# epd_board.net
KiCad netlist of a schematic drawn in EAGLE
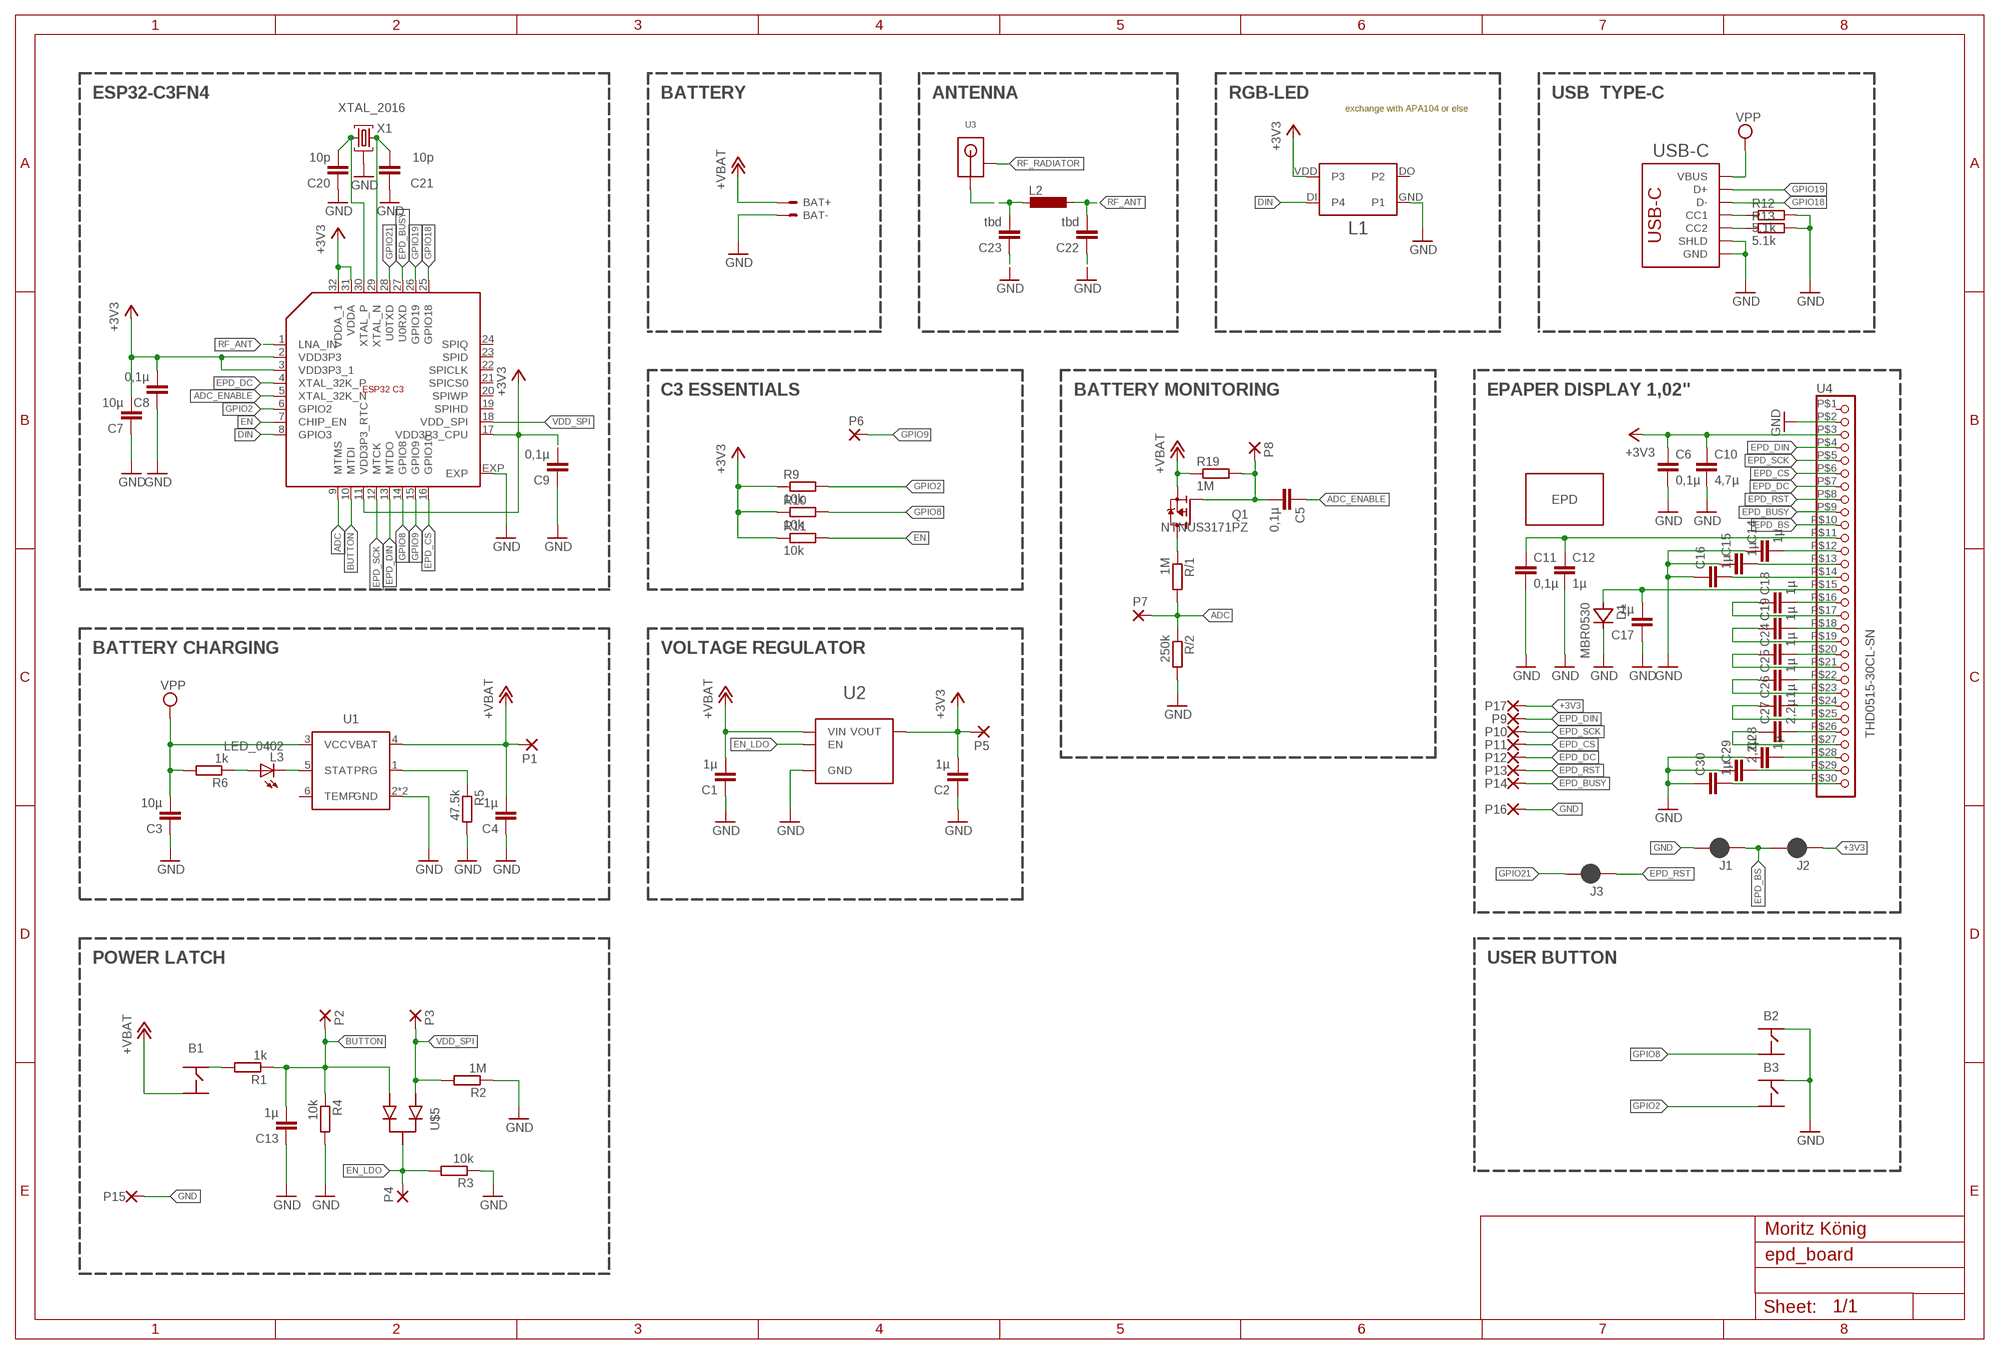
[diagram p0: schematic, sheet 1]

(export (version "E")
  (design (tool "Eeschema 10.0.6"))
  (components
    (comp (ref "B1")
      (value "BUTTON_4PIN_TS-1070A")
      (footprint "eagle-import:BUTTON_WHITE_SMD")
      (libsource (lib "eagle-import") (part "BUTTON_4PIN_TS-1070A"))
    )
    (comp (ref "B2")
      (value "PTS840ESDGMSMTRLFS")
      (footprint "eagle-import:PTS840ESDGMSMTRLFS")
      (libsource (lib "eagle-import") (part "PTS840ESDGMSMTRLFS"))
    )
    (comp (ref "B3")
      (value "PTS840ESDGMSMTRLFS")
      (footprint "eagle-import:PTS840ESDGMSMTRLFS")
      (libsource (lib "eagle-import") (part "PTS840ESDGMSMTRLFS"))
    )
    (comp (ref "BAT+")
      (value "TP/SP-1.5X1.0")
      (footprint "eagle-import:SOLDERPAD_1.5X1.0")
      (libsource (lib "eagle-import") (part "TP/SP-1.5X1.0"))
    )
    (comp (ref "BAT-")
      (value "TP/SP-1.5X1.0")
      (footprint "eagle-import:SOLDERPAD_1.5X1.0")
      (libsource (lib "eagle-import") (part "TP/SP-1.5X1.0"))
    )
    (comp (ref "C1")
      (value "1µ")
      (footprint "eagle-import:C0402_S")
      (libsource (lib "eagle-import") (part "C0402_S"))
    )
    (comp (ref "C2")
      (value "1µ")
      (footprint "eagle-import:C0402_S")
      (libsource (lib "eagle-import") (part "C0402_S"))
    )
    (comp (ref "C3")
      (value "10µ")
      (footprint "eagle-import:C0402_S")
      (libsource (lib "eagle-import") (part "C0402_S"))
    )
    (comp (ref "C4")
      (value "1µ")
      (footprint "eagle-import:C0402_S")
      (libsource (lib "eagle-import") (part "C0402_S"))
    )
    (comp (ref "C5")
      (value "0,1µ")
      (footprint "eagle-import:C0402_S")
      (libsource (lib "eagle-import") (part "C0402_S"))
    )
    (comp (ref "C6")
      (value "0,1µ")
      (footprint "eagle-import:C0402_S")
      (libsource (lib "eagle-import") (part "C0402_S"))
    )
    (comp (ref "C7")
      (value "10µ")
      (footprint "eagle-import:C0402_S")
      (libsource (lib "eagle-import") (part "C0402_S"))
    )
    (comp (ref "C8")
      (value "0,1µ")
      (footprint "eagle-import:C0402_S")
      (libsource (lib "eagle-import") (part "C0402_S"))
    )
    (comp (ref "C9")
      (value "0,1µ")
      (footprint "eagle-import:C0402_S")
      (libsource (lib "eagle-import") (part "C0402_S"))
    )
    (comp (ref "C10")
      (value "4,7µ")
      (footprint "eagle-import:C0402_S")
      (libsource (lib "eagle-import") (part "C0402_S"))
    )
    (comp (ref "C11")
      (value "0,1µ")
      (footprint "eagle-import:C0402_S")
      (libsource (lib "eagle-import") (part "C0402_S"))
    )
    (comp (ref "C12")
      (value "1µ")
      (footprint "eagle-import:C0402_S")
      (libsource (lib "eagle-import") (part "C0402_S"))
    )
    (comp (ref "C13")
      (value "1µ")
      (footprint "eagle-import:C0402_S")
      (libsource (lib "eagle-import") (part "C0402_S"))
    )
    (comp (ref "C14")
      (value "1µ")
      (footprint "eagle-import:C0402_S")
      (libsource (lib "eagle-import") (part "C0402_S"))
    )
    (comp (ref "C15")
      (value "1µ")
      (footprint "eagle-import:C0402_S")
      (libsource (lib "eagle-import") (part "C0402_S"))
    )
    (comp (ref "C16")
      (value "1µ")
      (footprint "eagle-import:C0402_S")
      (libsource (lib "eagle-import") (part "C0402_S"))
    )
    (comp (ref "C17")
      (value "1µ")
      (footprint "eagle-import:C0402_S")
      (libsource (lib "eagle-import") (part "C0402_S"))
    )
    (comp (ref "C18")
      (value "1µ")
      (footprint "eagle-import:C0402_S")
      (libsource (lib "eagle-import") (part "C0402_S"))
    )
    (comp (ref "C19")
      (value "1µ")
      (footprint "eagle-import:C0402_S")
      (libsource (lib "eagle-import") (part "C0402_S"))
    )
    (comp (ref "C20")
      (value "10p")
      (footprint "eagle-import:C0402_S")
      (libsource (lib "eagle-import") (part "C0402_S"))
    )
    (comp (ref "C21")
      (value "10p")
      (footprint "eagle-import:C0402_S")
      (libsource (lib "eagle-import") (part "C0402_S"))
    )
    (comp (ref "C22")
      (value "tbd")
      (footprint "eagle-import:C0201")
      (libsource (lib "eagle-import") (part "C0201"))
    )
    (comp (ref "C23")
      (value "tbd")
      (footprint "eagle-import:C0201")
      (libsource (lib "eagle-import") (part "C0201"))
    )
    (comp (ref "C24")
      (value "1µ")
      (footprint "eagle-import:C0402_S")
      (libsource (lib "eagle-import") (part "C0402_S"))
    )
    (comp (ref "C25")
      (value "1µ")
      (footprint "eagle-import:C0402_S")
      (libsource (lib "eagle-import") (part "C0402_S"))
    )
    (comp (ref "C26")
      (value "1µ")
      (footprint "eagle-import:C0402_S")
      (libsource (lib "eagle-import") (part "C0402_S"))
    )
    (comp (ref "C27")
      (value "2,2µ")
      (footprint "eagle-import:C0402_S")
      (libsource (lib "eagle-import") (part "C0402_S"))
    )
    (comp (ref "C28")
      (value "1µ")
      (footprint "eagle-import:C0402_S")
      (libsource (lib "eagle-import") (part "C0402_S"))
    )
    (comp (ref "C29")
      (value "2,2µ")
      (footprint "eagle-import:C0402_S")
      (libsource (lib "eagle-import") (part "C0402_S"))
    )
    (comp (ref "C30")
      (value "1µ")
      (footprint "eagle-import:C0402_S")
      (libsource (lib "eagle-import") (part "C0402_S"))
    )
    (comp (ref "D1")
      (value "MBR0530")
      (footprint "eagle-import:SOD123")
      (libsource (lib "eagle-import") (part "MBR0520"))
    )
    (comp (ref "ESP1")
      (value "ESP32_C3_QFN32")
      (footprint "eagle-import:QFN32")
      (libsource (lib "eagle-import") (part "ESP32_C3_QFN32"))
    )
    (comp (ref "J1")
      (value "SMT_JUMPER_2_NC_PASTE")
      (footprint "eagle-import:JUMPER_SMALL")
      (libsource (lib "eagle-import") (part "SMT_JUMPER_2_NC_PASTE"))
    )
    (comp (ref "J2")
      (value "SMT_JUMPER_2_NC_PASTE")
      (footprint "eagle-import:JUMPER_SMALL")
      (libsource (lib "eagle-import") (part "SMT_JUMPER_2_NC_PASTE"))
    )
    (comp (ref "J3")
      (value "SMT_JUMPER_2_NC_PASTE")
      (footprint "eagle-import:JUMPER_SMALL")
      (libsource (lib "eagle-import") (part "SMT_JUMPER_2_NC_PASTE"))
    )
    (comp (ref "L1")
      (value "WS2812_2020")
      (footprint "eagle-import:WS2812_2020")
      (libsource (lib "eagle-import") (part "WS2812_2020"))
    )
    (comp (ref "L2")
      (value "L0201")
      (footprint "eagle-import:L0201")
      (libsource (lib "eagle-import") (part "L0201"))
    )
    (comp (ref "L3")
      (value "LED_0402")
      (footprint "eagle-import:CHIPLED_0402")
      (libsource (lib "eagle-import") (part "LED_0402"))
    )
    (comp (ref "P1")
      (value "SMD-R1")
      (footprint "eagle-import:SMD-R1")
      (libsource (lib "eagle-import") (part "SMD-R1"))
    )
    (comp (ref "P2")
      (value "SMD-R1")
      (footprint "eagle-import:SMD-R1")
      (libsource (lib "eagle-import") (part "SMD-R1"))
    )
    (comp (ref "P3")
      (value "SMD-R1")
      (footprint "eagle-import:SMD-R1")
      (libsource (lib "eagle-import") (part "SMD-R1"))
    )
    (comp (ref "P4")
      (value "SMD-R1")
      (footprint "eagle-import:SMD-R1")
      (libsource (lib "eagle-import") (part "SMD-R1"))
    )
    (comp (ref "P5")
      (value "SMD-R1")
      (footprint "eagle-import:SMD-R1")
      (libsource (lib "eagle-import") (part "SMD-R1"))
    )
    (comp (ref "P6")
      (value "SMD-R1")
      (footprint "eagle-import:SMD-R1")
      (libsource (lib "eagle-import") (part "SMD-R1"))
    )
    (comp (ref "P7")
      (value "SMD-R1")
      (footprint "eagle-import:SMD-R1")
      (libsource (lib "eagle-import") (part "SMD-R1"))
    )
    (comp (ref "P8")
      (value "SMD-R1")
      (footprint "eagle-import:SMD-R1")
      (libsource (lib "eagle-import") (part "SMD-R1"))
    )
    (comp (ref "P9")
      (value "SMD-R1")
      (footprint "eagle-import:SMD-R1")
      (libsource (lib "eagle-import") (part "SMD-R1"))
    )
    (comp (ref "P10")
      (value "SMD-R1")
      (footprint "eagle-import:SMD-R1")
      (libsource (lib "eagle-import") (part "SMD-R1"))
    )
    (comp (ref "P11")
      (value "SMD-R1")
      (footprint "eagle-import:SMD-R1")
      (libsource (lib "eagle-import") (part "SMD-R1"))
    )
    (comp (ref "P12")
      (value "SMD-R1")
      (footprint "eagle-import:SMD-R1")
      (libsource (lib "eagle-import") (part "SMD-R1"))
    )
    (comp (ref "P13")
      (value "SMD-R1")
      (footprint "eagle-import:SMD-R1")
      (libsource (lib "eagle-import") (part "SMD-R1"))
    )
    (comp (ref "P14")
      (value "SMD-R1")
      (footprint "eagle-import:SMD-R1")
      (libsource (lib "eagle-import") (part "SMD-R1"))
    )
    (comp (ref "P15")
      (value "SMD-R1")
      (footprint "eagle-import:SMD-R1")
      (libsource (lib "eagle-import") (part "SMD-R1"))
    )
    (comp (ref "P16")
      (value "SMD-R1")
      (footprint "eagle-import:SMD-R1")
      (libsource (lib "eagle-import") (part "SMD-R1"))
    )
    (comp (ref "P17")
      (value "SMD-R1")
      (footprint "eagle-import:SMD-R1")
      (libsource (lib "eagle-import") (part "SMD-R1"))
    )
    (comp (ref "Q1")
      (value "NTNUS3171PZ")
      (footprint "eagle-import:SOT1123")
      (libsource (lib "eagle-import") (part "NTNUS3171PZ"))
    )
    (comp (ref "R/1")
      (value "1M")
      (footprint "eagle-import:R0402")
      (libsource (lib "eagle-import") (part "R0402"))
    )
    (comp (ref "R/2")
      (value "250k")
      (footprint "eagle-import:R0402")
      (libsource (lib "eagle-import") (part "R0402"))
    )
    (comp (ref "R1")
      (value "1k")
      (footprint "eagle-import:R0402")
      (libsource (lib "eagle-import") (part "R0402"))
    )
    (comp (ref "R2")
      (value "1M")
      (footprint "eagle-import:R0402")
      (libsource (lib "eagle-import") (part "R0402"))
    )
    (comp (ref "R3")
      (value "10k")
      (footprint "eagle-import:R0402")
      (libsource (lib "eagle-import") (part "R0402"))
    )
    (comp (ref "R4")
      (value "10k")
      (footprint "eagle-import:R0402")
      (libsource (lib "eagle-import") (part "R0402"))
    )
    (comp (ref "R5")
      (value "47.5k")
      (footprint "eagle-import:R0402")
      (libsource (lib "eagle-import") (part "R0402"))
    )
    (comp (ref "R6")
      (value "1k")
      (footprint "eagle-import:R0402")
      (libsource (lib "eagle-import") (part "R0402"))
    )
    (comp (ref "R9")
      (value "10k")
      (footprint "eagle-import:R0402")
      (libsource (lib "eagle-import") (part "R0402"))
    )
    (comp (ref "R10")
      (value "10k")
      (footprint "eagle-import:R0402")
      (libsource (lib "eagle-import") (part "R0402"))
    )
    (comp (ref "R11")
      (value "10k")
      (footprint "eagle-import:R0402")
      (libsource (lib "eagle-import") (part "R0402"))
    )
    (comp (ref "R12")
      (value "5.1k")
      (footprint "eagle-import:R0402")
      (libsource (lib "eagle-import") (part "R0402"))
    )
    (comp (ref "R13")
      (value "5.1k")
      (footprint "eagle-import:R0402")
      (libsource (lib "eagle-import") (part "R0402"))
    )
    (comp (ref "R19")
      (value "1M")
      (footprint "eagle-import:R0402")
      (libsource (lib "eagle-import") (part "R0402"))
    )
    (comp (ref "U$2")
      (value "EPD-102-30PIN-TW")
      (footprint "eagle-import:EPD-102-30PIN-TW")
      (libsource (lib "eagle-import") (part "EPD-102-30PIN-TW"))
    )
    (comp (ref "U$5")
      (value "DAN222")
      (footprint "eagle-import:SOT523")
      (libsource (lib "eagle-import") (part "DAN222"))
    )
    (comp (ref "U1")
      (value "WS4518D")
      (footprint "eagle-import:DFN-6")
      (libsource (lib "eagle-import") (part "WS4518D"))
    )
    (comp (ref "U2")
      (value "MIC5504")
      (footprint "eagle-import:TDFN4")
      (libsource (lib "eagle-import") (part "MIC5504"))
    )
    (comp (ref "U3")
      (value "ANT016008LCS2442MA2")
      (footprint "eagle-import:ANT016008LCS2442MA2")
      (libsource (lib "eagle-import") (part "ANT016008LCS2442MA2"))
    )
    (comp (ref "U4")
      (value "THD0515-30CL-SN")
      (footprint "eagle-import:THD0515-30CL-SN")
      (libsource (lib "eagle-import") (part "THD0515-30CL-SN"))
    )
    (comp (ref "USB-C")
      (value "USB_C_C393939")
      (footprint "eagle-import:USBC_C393939")
      (libsource (lib "eagle-import") (part "USB_C_C393939"))
    )
    (comp (ref "X1")
      (value "XTAL_2016")
      (footprint "eagle-import:XTAL_2016")
      (libsource (lib "eagle-import") (part "XTAL_2016"))
    )
  )
  (nets
    (net (code "1") (name "+3V3") (class "Default")
      (node (ref "C10") (pin "P$1") (pinfunction "1_P$1") (pintype "passive"))
      (node (ref "C2") (pin "P$2") (pinfunction "2_P$2") (pintype "passive"))
      (node (ref "C6") (pin "P$1") (pinfunction "1_P$1") (pintype "passive"))
      (node (ref "C7") (pin "P$2") (pinfunction "2_P$2") (pintype "passive"))
      (node (ref "C8") (pin "P$2") (pinfunction "2_P$2") (pintype "passive"))
      (node (ref "C9") (pin "P$2") (pinfunction "2_P$2") (pintype "passive"))
      (node (ref "ESP1") (pin "11") (pinfunction "VDD3P3_RTC_11") (pintype "bidirectional"))
      (node (ref "ESP1") (pin "17") (pinfunction "VDD3P3_CPU_17") (pintype "bidirectional"))
      (node (ref "ESP1") (pin "2") (pinfunction "VDD3P3_2") (pintype "bidirectional"))
      (node (ref "ESP1") (pin "3") (pinfunction "VDD3P3_1_3") (pintype "bidirectional"))
      (node (ref "ESP1") (pin "31") (pinfunction "VDDA_31") (pintype "bidirectional"))
      (node (ref "ESP1") (pin "32") (pinfunction "VDDA_1_32") (pintype "bidirectional"))
      (node (ref "J2") (pin "P$1") (pinfunction "1_P$1") (pintype "passive"))
      (node (ref "L1") (pin "VDD") (pinfunction "P3_VDD") (pintype "bidirectional"))
      (node (ref "P17") (pin "P$1") (pinfunction "P_P$1") (pintype "passive"))
      (node (ref "P5") (pin "P$1") (pinfunction "P_P$1") (pintype "passive"))
      (node (ref "R10") (pin "1") (pinfunction "1_1") (pintype "passive"))
      (node (ref "R11") (pin "1") (pinfunction "1_1") (pintype "passive"))
      (node (ref "R9") (pin "1") (pinfunction "1_1") (pintype "passive"))
      (node (ref "U2") (pin "P1") (pinfunction "VOUT_P1") (pintype "bidirectional"))
      (node (ref "U4") (pin "P$3") (pinfunction "3_P$3") (pintype "passive"))
    )
    (net (code "2") (name "+VBAT") (class "Default")
      (node (ref "B1") (pin "P$2") (pinfunction "3_P$2") (pintype "bidirectional"))
      (node (ref "BAT+") (pin "1") (pinfunction "S_1") (pintype "passive"))
      (node (ref "C1") (pin "P$2") (pinfunction "2_P$2") (pintype "passive"))
      (node (ref "C4") (pin "P$2") (pinfunction "2_P$2") (pintype "passive"))
      (node (ref "P1") (pin "P$1") (pinfunction "P_P$1") (pintype "passive"))
      (node (ref "Q1") (pin "2") (pinfunction "S_2") (pintype "passive"))
      (node (ref "R19") (pin "1") (pinfunction "1_1") (pintype "passive"))
      (node (ref "U1") (pin "4") (pinfunction "VBAT_4") (pintype "bidirectional"))
      (node (ref "U2") (pin "P4") (pinfunction "VIN_P4") (pintype "bidirectional"))
    )
    (net (code "3") (name "ADC") (class "Default")
      (node (ref "ESP1") (pin "9") (pinfunction "MTMS_9") (pintype "bidirectional"))
      (node (ref "P7") (pin "P$1") (pinfunction "P_P$1") (pintype "passive"))
      (node (ref "R/1") (pin "2") (pinfunction "2_2") (pintype "passive"))
      (node (ref "R/2") (pin "1") (pinfunction "1_1") (pintype "passive"))
    )
    (net (code "4") (name "ADC_ENABLE") (class "Default")
      (node (ref "C5") (pin "P$1") (pinfunction "1_P$1") (pintype "passive"))
      (node (ref "ESP1") (pin "5") (pinfunction "XTAL_32K_N_5") (pintype "bidirectional"))
    )
    (net (code "5") (name "BUTTON") (class "Default")
      (node (ref "C13") (pin "P$2") (pinfunction "2_P$2") (pintype "passive"))
      (node (ref "ESP1") (pin "10") (pinfunction "MTDI_10") (pintype "bidirectional"))
      (node (ref "P2") (pin "P$1") (pinfunction "P_P$1") (pintype "passive"))
      (node (ref "R1") (pin "1") (pinfunction "1_1") (pintype "passive"))
      (node (ref "R4") (pin "1") (pinfunction "1_1") (pintype "passive"))
      (node (ref "U$5") (pin "2") (pinfunction "2_2") (pintype "bidirectional"))
    )
    (net (code "6") (name "DIN") (class "Default")
      (node (ref "ESP1") (pin "8") (pinfunction "GPIO3_8") (pintype "bidirectional"))
      (node (ref "L1") (pin "DI") (pinfunction "P4_DI") (pintype "bidirectional"))
    )
    (net (code "7") (name "EN") (class "Default")
      (node (ref "ESP1") (pin "7") (pinfunction "CHIP_EN_7") (pintype "bidirectional"))
      (node (ref "R11") (pin "2") (pinfunction "2_2") (pintype "passive"))
    )
    (net (code "8") (name "EN_LDO") (class "Default")
      (node (ref "P4") (pin "P$1") (pinfunction "P_P$1") (pintype "passive"))
      (node (ref "R3") (pin "2") (pinfunction "2_2") (pintype "passive"))
      (node (ref "U$5") (pin "3") (pinfunction "3_3") (pintype "bidirectional"))
      (node (ref "U2") (pin "P3") (pinfunction "EN_P3") (pintype "bidirectional"))
    )
    (net (code "9") (name "EPD_BS") (class "Default")
      (node (ref "J1") (pin "P$1") (pinfunction "1_P$1") (pintype "passive"))
      (node (ref "J2") (pin "P$2") (pinfunction "2_P$2") (pintype "passive"))
      (node (ref "U4") (pin "P$10") (pinfunction "10_P$10") (pintype "passive"))
    )
    (net (code "10") (name "EPD_BUSY") (class "Default")
      (node (ref "ESP1") (pin "27") (pinfunction "U0RXD_27") (pintype "bidirectional"))
      (node (ref "P14") (pin "P$1") (pinfunction "P_P$1") (pintype "passive"))
      (node (ref "U4") (pin "P$9") (pinfunction "9_P$9") (pintype "passive"))
    )
    (net (code "11") (name "EPD_CS") (class "Default")
      (node (ref "ESP1") (pin "16") (pinfunction "GPIO10_16") (pintype "bidirectional"))
      (node (ref "P11") (pin "P$1") (pinfunction "P_P$1") (pintype "passive"))
      (node (ref "U4") (pin "P$6") (pinfunction "6_P$6") (pintype "passive"))
    )
    (net (code "12") (name "EPD_DC") (class "Default")
      (node (ref "ESP1") (pin "4") (pinfunction "XTAL_32K_P_4") (pintype "bidirectional"))
      (node (ref "P12") (pin "P$1") (pinfunction "P_P$1") (pintype "passive"))
      (node (ref "U4") (pin "P$7") (pinfunction "7_P$7") (pintype "passive"))
    )
    (net (code "13") (name "EPD_DIN") (class "Default")
      (node (ref "ESP1") (pin "13") (pinfunction "MTDO_13") (pintype "bidirectional"))
      (node (ref "P9") (pin "P$1") (pinfunction "P_P$1") (pintype "passive"))
      (node (ref "U4") (pin "P$4") (pinfunction "4_P$4") (pintype "passive"))
    )
    (net (code "14") (name "EPD_RST") (class "Default")
      (node (ref "J3") (pin "P$1") (pinfunction "1_P$1") (pintype "passive"))
      (node (ref "P13") (pin "P$1") (pinfunction "P_P$1") (pintype "passive"))
      (node (ref "U4") (pin "P$8") (pinfunction "8_P$8") (pintype "passive"))
    )
    (net (code "15") (name "EPD_SCK") (class "Default")
      (node (ref "ESP1") (pin "12") (pinfunction "MTCK_12") (pintype "bidirectional"))
      (node (ref "P10") (pin "P$1") (pinfunction "P_P$1") (pintype "passive"))
      (node (ref "U4") (pin "P$5") (pinfunction "5_P$5") (pintype "passive"))
    )
    (net (code "16") (name "GND") (class "Default")
      (node (ref "B2") (pin "2") (pinfunction "2_2") (pintype "bidirectional"))
      (node (ref "B3") (pin "2") (pinfunction "2_2") (pintype "bidirectional"))
      (node (ref "BAT-") (pin "1") (pinfunction "S_1") (pintype "passive"))
      (node (ref "C1") (pin "P$1") (pinfunction "1_P$1") (pintype "passive"))
      (node (ref "C10") (pin "P$2") (pinfunction "2_P$2") (pintype "passive"))
      (node (ref "C11") (pin "P$2") (pinfunction "2_P$2") (pintype "passive"))
      (node (ref "C12") (pin "P$2") (pinfunction "2_P$2") (pintype "passive"))
      (node (ref "C13") (pin "P$1") (pinfunction "1_P$1") (pintype "passive"))
      (node (ref "C14") (pin "P$1") (pinfunction "1_P$1") (pintype "passive"))
      (node (ref "C15") (pin "P$1") (pinfunction "1_P$1") (pintype "passive"))
      (node (ref "C16") (pin "P$1") (pinfunction "1_P$1") (pintype "passive"))
      (node (ref "C17") (pin "P$1") (pinfunction "1_P$1") (pintype "passive"))
      (node (ref "C2") (pin "P$1") (pinfunction "1_P$1") (pintype "passive"))
      (node (ref "C20") (pin "P$1") (pinfunction "1_P$1") (pintype "passive"))
      (node (ref "C21") (pin "P$1") (pinfunction "1_P$1") (pintype "passive"))
      (node (ref "C22") (pin "P$1") (pinfunction "1_P$1") (pintype "passive"))
      (node (ref "C23") (pin "P$1") (pinfunction "1_P$1") (pintype "passive"))
      (node (ref "C28") (pin "P$1") (pinfunction "1_P$1") (pintype "passive"))
      (node (ref "C29") (pin "P$1") (pinfunction "1_P$1") (pintype "passive"))
      (node (ref "C3") (pin "P$1") (pinfunction "1_P$1") (pintype "passive"))
      (node (ref "C30") (pin "P$1") (pinfunction "1_P$1") (pintype "passive"))
      (node (ref "C4") (pin "P$1") (pinfunction "1_P$1") (pintype "passive"))
      (node (ref "C6") (pin "P$2") (pinfunction "2_P$2") (pintype "passive"))
      (node (ref "C7") (pin "P$1") (pinfunction "1_P$1") (pintype "passive"))
      (node (ref "C8") (pin "P$1") (pinfunction "1_P$1") (pintype "passive"))
      (node (ref "C9") (pin "P$1") (pinfunction "1_P$1") (pintype "passive"))
      (node (ref "D1") (pin "P$2") (pinfunction "C_P$2") (pintype "passive"))
      (node (ref "ESP1") (pin "EXP") (pinfunction "EXP_EXP") (pintype "bidirectional"))
      (node (ref "J1") (pin "P$2") (pinfunction "2_P$2") (pintype "passive"))
      (node (ref "L1") (pin "GND") (pinfunction "P1_GND") (pintype "bidirectional"))
      (node (ref "P15") (pin "P$1") (pinfunction "P_P$1") (pintype "passive"))
      (node (ref "P16") (pin "P$1") (pinfunction "P_P$1") (pintype "passive"))
      (node (ref "R/2") (pin "2") (pinfunction "2_2") (pintype "passive"))
      (node (ref "R12") (pin "2") (pinfunction "2_2") (pintype "passive"))
      (node (ref "R13") (pin "2") (pinfunction "2_2") (pintype "passive"))
      (node (ref "R2") (pin "1") (pinfunction "1_1") (pintype "passive"))
      (node (ref "R3") (pin "1") (pinfunction "1_1") (pintype "passive"))
      (node (ref "R4") (pin "2") (pinfunction "2_2") (pintype "passive"))
      (node (ref "R5") (pin "2") (pinfunction "2_2") (pintype "passive"))
      (node (ref "U1") (pin "2") (pinfunction "GND_2") (pintype "bidirectional"))
      (node (ref "U1") (pin "EXP") (pinfunction "GND_EXP") (pintype "bidirectional"))
      (node (ref "U2") (pin "EXP") (pinfunction "GND_EXP") (pintype "bidirectional"))
      (node (ref "U2") (pin "P2") (pinfunction "GND_P2") (pintype "bidirectional"))
      (node (ref "U4") (pin "P$2") (pinfunction "2_P$2") (pintype "passive"))
      (node (ref "USB-C") (pin "A1B12") (pinfunction "GND_A1B12") (pintype "bidirectional"))
      (node (ref "USB-C") (pin "B1A12") (pinfunction "GND_B1A12") (pintype "bidirectional"))
      (node (ref "USB-C") (pin "S1") (pinfunction "SHLD_S1") (pintype "bidirectional"))
      (node (ref "USB-C") (pin "S2") (pinfunction "SHLD_S2") (pintype "bidirectional"))
      (node (ref "USB-C") (pin "S3") (pinfunction "SHLD_S3") (pintype "bidirectional"))
      (node (ref "USB-C") (pin "S4") (pinfunction "SHLD_S4") (pintype "bidirectional"))
      (node (ref "X1") (pin "P2") (pinfunction "G_P2") (pintype "passive"))
      (node (ref "X1") (pin "P4") (pinfunction "G_P4") (pintype "passive"))
    )
    (net (code "17") (name "GPIO2") (class "Default")
      (node (ref "B3") (pin "3") (pinfunction "3_3") (pintype "bidirectional"))
      (node (ref "ESP1") (pin "6") (pinfunction "GPIO2_6") (pintype "bidirectional"))
      (node (ref "R9") (pin "2") (pinfunction "2_2") (pintype "passive"))
    )
    (net (code "18") (name "GPIO8") (class "Default")
      (node (ref "B2") (pin "3") (pinfunction "3_3") (pintype "bidirectional"))
      (node (ref "ESP1") (pin "14") (pinfunction "GPIO8_14") (pintype "bidirectional"))
      (node (ref "R10") (pin "2") (pinfunction "2_2") (pintype "passive"))
    )
    (net (code "19") (name "GPIO9") (class "Default")
      (node (ref "ESP1") (pin "15") (pinfunction "GPIO9_15") (pintype "bidirectional"))
      (node (ref "P6") (pin "P$1") (pinfunction "P_P$1") (pintype "passive"))
    )
    (net (code "20") (name "GPIO18") (class "Default")
      (node (ref "ESP1") (pin "25") (pinfunction "GPIO18_25") (pintype "bidirectional"))
      (node (ref "USB-C") (pin "A7") (pinfunction "D-_A7") (pintype "bidirectional"))
      (node (ref "USB-C") (pin "B7") (pinfunction "D-_B7") (pintype "bidirectional"))
    )
    (net (code "21") (name "GPIO19") (class "Default")
      (node (ref "ESP1") (pin "26") (pinfunction "GPIO19_26") (pintype "bidirectional"))
      (node (ref "USB-C") (pin "A6") (pinfunction "D+_A6") (pintype "bidirectional"))
      (node (ref "USB-C") (pin "B6") (pinfunction "D+_B6") (pintype "bidirectional"))
    )
    (net (code "22") (name "GPIO21") (class "Default")
      (node (ref "ESP1") (pin "28") (pinfunction "U0TXD_28") (pintype "bidirectional"))
      (node (ref "J3") (pin "P$2") (pinfunction "2_P$2") (pintype "passive"))
    )
    (net (code "23") (name "Net-(B1-2)") (class "Default")
      (node (ref "B1") (pin "P$4") (pinfunction "2_P$4") (pintype "bidirectional"))
      (node (ref "R1") (pin "2") (pinfunction "2_2") (pintype "passive"))
    )
    (net (code "24") (name "Net-(C5-2)") (class "Default")
      (node (ref "C5") (pin "P$2") (pinfunction "2_P$2") (pintype "passive"))
      (node (ref "P8") (pin "P$1") (pinfunction "P_P$1") (pintype "passive"))
      (node (ref "Q1") (pin "1") (pinfunction "G_1") (pintype "passive"))
      (node (ref "R19") (pin "2") (pinfunction "2_2") (pintype "passive"))
    )
    (net (code "25") (name "Net-(C11-1)") (class "Default")
      (node (ref "C11") (pin "P$1") (pinfunction "1_P$1") (pintype "passive"))
      (node (ref "C12") (pin "P$1") (pinfunction "1_P$1") (pintype "passive"))
      (node (ref "U4") (pin "P$11") (pinfunction "11_P$11") (pintype "passive"))
    )
    (net (code "26") (name "Net-(C14-2)") (class "Default")
      (node (ref "C14") (pin "P$2") (pinfunction "2_P$2") (pintype "passive"))
      (node (ref "U4") (pin "P$12") (pinfunction "12_P$12") (pintype "passive"))
    )
    (net (code "27") (name "Net-(C15-2)") (class "Default")
      (node (ref "C15") (pin "P$2") (pinfunction "2_P$2") (pintype "passive"))
      (node (ref "U4") (pin "P$13") (pinfunction "13_P$13") (pintype "passive"))
    )
    (net (code "28") (name "Net-(C16-2)") (class "Default")
      (node (ref "C16") (pin "P$2") (pinfunction "2_P$2") (pintype "passive"))
      (node (ref "U4") (pin "P$14") (pinfunction "14_P$14") (pintype "passive"))
    )
    (net (code "29") (name "Net-(C17-2)") (class "Default")
      (node (ref "C17") (pin "P$2") (pinfunction "2_P$2") (pintype "passive"))
      (node (ref "D1") (pin "P$1") (pinfunction "A_P$1") (pintype "passive"))
      (node (ref "U4") (pin "P$15") (pinfunction "15_P$15") (pintype "passive"))
    )
    (net (code "30") (name "Net-(C18-1)") (class "Default")
      (node (ref "C18") (pin "P$1") (pinfunction "1_P$1") (pintype "passive"))
      (node (ref "U4") (pin "P$17") (pinfunction "17_P$17") (pintype "passive"))
    )
    (net (code "31") (name "Net-(C18-2)") (class "Default")
      (node (ref "C18") (pin "P$2") (pinfunction "2_P$2") (pintype "passive"))
      (node (ref "U4") (pin "P$16") (pinfunction "16_P$16") (pintype "passive"))
    )
    (net (code "32") (name "Net-(C19-1)") (class "Default")
      (node (ref "C19") (pin "P$1") (pinfunction "1_P$1") (pintype "passive"))
      (node (ref "U4") (pin "P$19") (pinfunction "19_P$19") (pintype "passive"))
    )
    (net (code "33") (name "Net-(C19-2)") (class "Default")
      (node (ref "C19") (pin "P$2") (pinfunction "2_P$2") (pintype "passive"))
      (node (ref "U4") (pin "P$18") (pinfunction "18_P$18") (pintype "passive"))
    )
    (net (code "34") (name "Net-(C20-2)") (class "Default")
      (node (ref "C20") (pin "P$2") (pinfunction "2_P$2") (pintype "passive"))
      (node (ref "ESP1") (pin "30") (pinfunction "XTAL_P_30") (pintype "bidirectional"))
      (node (ref "X1") (pin "P1") (pinfunction "1_P1") (pintype "passive"))
    )
    (net (code "35") (name "Net-(C21-2)") (class "Default")
      (node (ref "C21") (pin "P$2") (pinfunction "2_P$2") (pintype "passive"))
      (node (ref "ESP1") (pin "29") (pinfunction "XTAL_N_29") (pintype "bidirectional"))
      (node (ref "X1") (pin "P3") (pinfunction "2_P3") (pintype "passive"))
    )
    (net (code "36") (name "Net-(C23-2)") (class "Default")
      (node (ref "C23") (pin "P$2") (pinfunction "2_P$2") (pintype "passive"))
      (node (ref "L2") (pin "P$2") (pinfunction "2_P$2") (pintype "passive"))
      (node (ref "U3") (pin "3") (pinfunction "ANT_3") (pintype "bidirectional"))
    )
    (net (code "37") (name "Net-(C24-1)") (class "Default")
      (node (ref "C24") (pin "P$1") (pinfunction "1_P$1") (pintype "passive"))
      (node (ref "U4") (pin "P$21") (pinfunction "21_P$21") (pintype "passive"))
    )
    (net (code "38") (name "Net-(C24-2)") (class "Default")
      (node (ref "C24") (pin "P$2") (pinfunction "2_P$2") (pintype "passive"))
      (node (ref "U4") (pin "P$20") (pinfunction "20_P$20") (pintype "passive"))
    )
    (net (code "39") (name "Net-(C25-1)") (class "Default")
      (node (ref "C25") (pin "P$1") (pinfunction "1_P$1") (pintype "passive"))
      (node (ref "U4") (pin "P$23") (pinfunction "23_P$23") (pintype "passive"))
    )
    (net (code "40") (name "Net-(C25-2)") (class "Default")
      (node (ref "C25") (pin "P$2") (pinfunction "2_P$2") (pintype "passive"))
      (node (ref "U4") (pin "P$22") (pinfunction "22_P$22") (pintype "passive"))
    )
    (net (code "41") (name "Net-(C26-1)") (class "Default")
      (node (ref "C26") (pin "P$1") (pinfunction "1_P$1") (pintype "passive"))
      (node (ref "U4") (pin "P$25") (pinfunction "25_P$25") (pintype "passive"))
    )
    (net (code "42") (name "Net-(C26-2)") (class "Default")
      (node (ref "C26") (pin "P$2") (pinfunction "2_P$2") (pintype "passive"))
      (node (ref "U4") (pin "P$24") (pinfunction "24_P$24") (pintype "passive"))
    )
    (net (code "43") (name "Net-(C27-1)") (class "Default")
      (node (ref "C27") (pin "P$1") (pinfunction "1_P$1") (pintype "passive"))
      (node (ref "U4") (pin "P$27") (pinfunction "27_P$27") (pintype "passive"))
    )
    (net (code "44") (name "Net-(C27-2)") (class "Default")
      (node (ref "C27") (pin "P$2") (pinfunction "2_P$2") (pintype "passive"))
      (node (ref "U4") (pin "P$26") (pinfunction "26_P$26") (pintype "passive"))
    )
    (net (code "45") (name "Net-(C28-2)") (class "Default")
      (node (ref "C28") (pin "P$2") (pinfunction "2_P$2") (pintype "passive"))
      (node (ref "U4") (pin "P$28") (pinfunction "28_P$28") (pintype "passive"))
    )
    (net (code "46") (name "Net-(C29-2)") (class "Default")
      (node (ref "C29") (pin "P$2") (pinfunction "2_P$2") (pintype "passive"))
      (node (ref "U4") (pin "P$29") (pinfunction "29_P$29") (pintype "passive"))
    )
    (net (code "47") (name "Net-(C30-2)") (class "Default")
      (node (ref "C30") (pin "P$2") (pinfunction "2_P$2") (pintype "passive"))
      (node (ref "U4") (pin "P$30") (pinfunction "30_P$30") (pintype "passive"))
    )
    (net (code "48") (name "Net-(L3-A)") (class "Default")
      (node (ref "L3") (pin "P$2") (pinfunction "A_P$2") (pintype "passive"))
      (node (ref "R6") (pin "1") (pinfunction "1_1") (pintype "passive"))
    )
    (net (code "49") (name "Net-(L3-C)") (class "Default")
      (node (ref "L3") (pin "P$1") (pinfunction "C_P$1") (pintype "passive"))
      (node (ref "U1") (pin "5") (pinfunction "STAT_5") (pintype "bidirectional"))
    )
    (net (code "50") (name "Net-(Q1-D)") (class "Default")
      (node (ref "Q1") (pin "3") (pinfunction "D_3") (pintype "passive"))
      (node (ref "R/1") (pin "1") (pinfunction "1_1") (pintype "passive"))
    )
    (net (code "51") (name "Net-(U1-PRG)") (class "Default")
      (node (ref "R5") (pin "1") (pinfunction "1_1") (pintype "passive"))
      (node (ref "U1") (pin "1") (pinfunction "PRG_1") (pintype "bidirectional"))
    )
    (net (code "52") (name "Net-(USB-C-CC1)") (class "Default")
      (node (ref "R12") (pin "1") (pinfunction "1_1") (pintype "passive"))
      (node (ref "USB-C") (pin "A5") (pinfunction "CC1_A5") (pintype "bidirectional"))
    )
    (net (code "53") (name "Net-(USB-C-CC2)") (class "Default")
      (node (ref "R13") (pin "1") (pinfunction "1_1") (pintype "passive"))
      (node (ref "USB-C") (pin "B5") (pinfunction "CC2_B5") (pintype "bidirectional"))
    )
    (net (code "54") (name "RF_ANT") (class "Default")
      (node (ref "C22") (pin "P$2") (pinfunction "2_P$2") (pintype "passive"))
      (node (ref "ESP1") (pin "1") (pinfunction "LNA_IN_1") (pintype "bidirectional"))
      (node (ref "L2") (pin "P$1") (pinfunction "1_P$1") (pintype "passive"))
    )
    (net (code "55") (name "RF_RADIATOR") (class "Default")
      (node (ref "U3") (pin "1") (pinfunction "GND_1") (pintype "bidirectional"))
    )
    (net (code "56") (name "VDD_SPI") (class "Default")
      (node (ref "ESP1") (pin "18") (pinfunction "VDD_SPI_18") (pintype "bidirectional"))
      (node (ref "P3") (pin "P$1") (pinfunction "P_P$1") (pintype "passive"))
      (node (ref "R2") (pin "2") (pinfunction "2_2") (pintype "passive"))
      (node (ref "U$5") (pin "1") (pinfunction "1_1") (pintype "bidirectional"))
    )
    (net (code "57") (name "VPP") (class "Default")
      (node (ref "C3") (pin "P$2") (pinfunction "2_P$2") (pintype "passive"))
      (node (ref "R6") (pin "2") (pinfunction "2_2") (pintype "passive"))
      (node (ref "U1") (pin "3") (pinfunction "VCC_3") (pintype "bidirectional"))
      (node (ref "USB-C") (pin "A4B9") (pinfunction "VBUS_A4B9") (pintype "bidirectional"))
      (node (ref "USB-C") (pin "B4A9") (pinfunction "VBUS_B4A9") (pintype "bidirectional"))
    )
    (net (code "58") (name "unconnected-(B1-1-PadP$1)") (class "Default")
      (node (ref "B1") (pin "P$1") (pinfunction "1_P$1") (pintype "bidirectional"))
    )
    (net (code "59") (name "unconnected-(B1-4-PadP$3)") (class "Default")
      (node (ref "B1") (pin "P$3") (pinfunction "4_P$3") (pintype "bidirectional"))
    )
    (net (code "60") (name "unconnected-(B2-Pad1)") (class "Default")
      (node (ref "B2") (pin "1") (pinfunction "1_1") (pintype "bidirectional"))
    )
    (net (code "61") (name "unconnected-(B2-Pad4)") (class "Default")
      (node (ref "B2") (pin "4") (pinfunction "4_4") (pintype "bidirectional"))
    )
    (net (code "62") (name "unconnected-(B2-Pad5)") (class "Default")
      (node (ref "B2") (pin "5") (pinfunction "5_5") (pintype "bidirectional"))
    )
    (net (code "63") (name "unconnected-(B3-Pad1)") (class "Default")
      (node (ref "B3") (pin "1") (pinfunction "1_1") (pintype "bidirectional"))
    )
    (net (code "64") (name "unconnected-(B3-Pad4)") (class "Default")
      (node (ref "B3") (pin "4") (pinfunction "4_4") (pintype "bidirectional"))
    )
    (net (code "65") (name "unconnected-(B3-Pad5)") (class "Default")
      (node (ref "B3") (pin "5") (pinfunction "5_5") (pintype "bidirectional"))
    )
    (net (code "66") (name "unconnected-(ESP1-SPICLK-Pad22)") (class "Default")
      (node (ref "ESP1") (pin "22") (pinfunction "SPICLK_22") (pintype "bidirectional"))
    )
    (net (code "67") (name "unconnected-(ESP1-SPICS0-Pad21)") (class "Default")
      (node (ref "ESP1") (pin "21") (pinfunction "SPICS0_21") (pintype "bidirectional"))
    )
    (net (code "68") (name "unconnected-(ESP1-SPID-Pad23)") (class "Default")
      (node (ref "ESP1") (pin "23") (pinfunction "SPID_23") (pintype "bidirectional"))
    )
    (net (code "69") (name "unconnected-(ESP1-SPIHD-Pad19)") (class "Default")
      (node (ref "ESP1") (pin "19") (pinfunction "SPIHD_19") (pintype "bidirectional"))
    )
    (net (code "70") (name "unconnected-(ESP1-SPIQ-Pad24)") (class "Default")
      (node (ref "ESP1") (pin "24") (pinfunction "SPIQ_24") (pintype "bidirectional"))
    )
    (net (code "71") (name "unconnected-(ESP1-SPIWP-Pad20)") (class "Default")
      (node (ref "ESP1") (pin "20") (pinfunction "SPIWP_20") (pintype "bidirectional"))
    )
    (net (code "72") (name "unconnected-(L1-P2-PadDO)") (class "Default")
      (node (ref "L1") (pin "DO") (pinfunction "P2_DO") (pintype "bidirectional"))
    )
    (net (code "73") (name "unconnected-(U1-TEMP-Pad6)") (class "Default")
      (node (ref "U1") (pin "6") (pinfunction "TEMP_6") (pintype "bidirectional"))
    )
    (net (code "74") (name "unconnected-(U4-1-PadP$1)") (class "Default")
      (node (ref "U4") (pin "P$1") (pinfunction "1_P$1") (pintype "passive"))
    )
  )
)
